# LEDclock_DCF77-RTC-BAT_2026-05-17.net
KiCad netlist of a schematic drawn in EasyEDA Pro
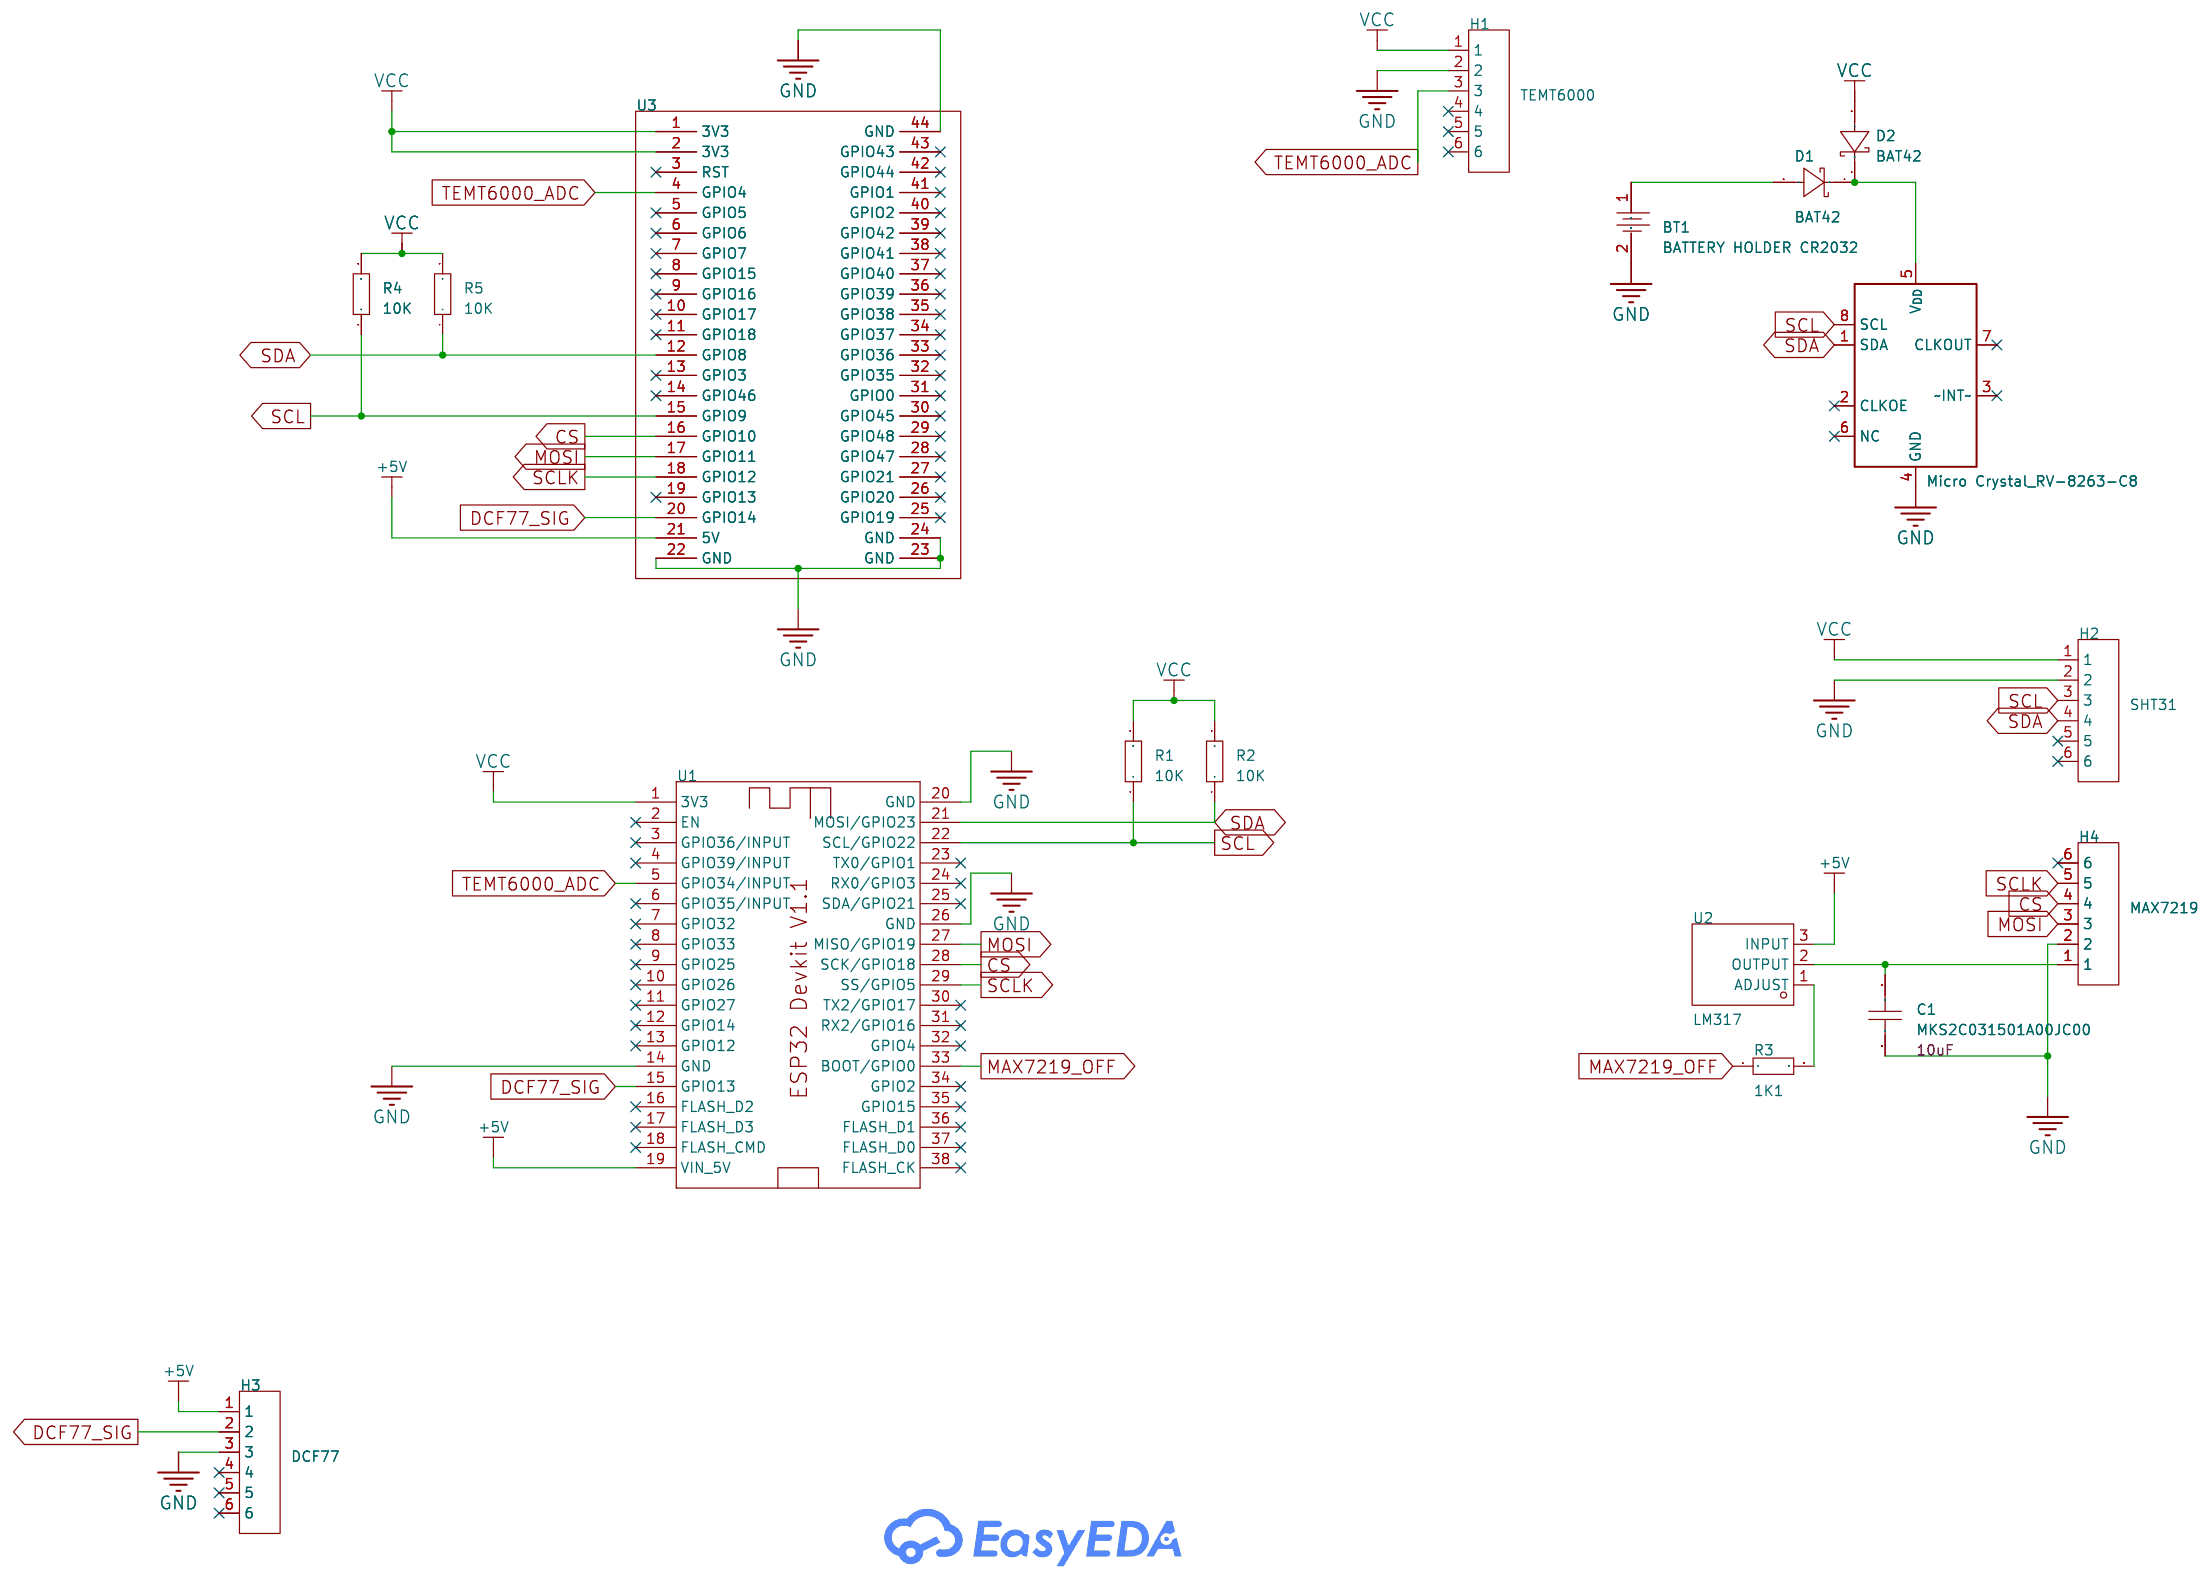
[diagram p0: schematic sheet]

(export (version "E")
  (design (tool "Eeschema 10.0.6"))
  (components
    (comp (ref "BT1")
      (value "BATTERY HOLDER CR2032")
      (footprint "easyedapro:BAT-TH_FBA25014-S02B2004K")
      (fields
        (field (name "Manufacturer Part") "FBA25014-S02B2004K")
        (field (name "Manufacturer") "TXGA(特思嘉)")
      )
      (libsource (lib "easyedapro") (part "FBA25014-S02B2004K"))
    )
    (comp (ref "C1")
      (value "MKS2C031501A00JC00")
      (footprint "easyedapro:CAP-TH_L7.2-W2.5-P5.00-D0.5-1")
      (fields (field (name "Manufacturer") "WIMA") (field (name "Capacitance") "10uF"))
      (libsource (lib "easyedapro") (part "MKS2C031501A00JC00"))
    )
    (comp (ref "D1")
      (value "BAT42")
      (footprint "easyedapro:DO-35_BD1.8-L4.1-P7.00-D0.5-RD")
      (fields (field (name "Manufacturer") "ST(意法半导体)"))
      (libsource (lib "easyedapro") (part "BAT42"))
    )
    (comp (ref "D2")
      (value "BAT42")
      (footprint "easyedapro:DO-35_BD1.8-L4.1-P7.00-D0.5-RD")
      (fields (field (name "Manufacturer") "ST(意法半导体)"))
      (libsource (lib "easyedapro") (part "BAT42"))
    )
    (comp (ref "H1")
      (value "TEMT6000")
      (footprint "easyedapro:CONN-TH_SSQ-106-03-G-S")
      (fields (field (name "Manufacturer") "SAMTEC"))
      (libsource (lib "easyedapro") (part "SSQ-106-03-G-S"))
    )
    (comp (ref "H2")
      (value "SHT31")
      (footprint "easyedapro:CONN-TH_SSQ-106-03-G-S")
      (fields (field (name "Manufacturer") "SAMTEC"))
      (libsource (lib "easyedapro") (part "SSQ-106-03-G-S"))
    )
    (comp (ref "H3")
      (value "DCF77")
      (footprint "easyedapro:CONN-TH_SSQ-106-03-G-S")
      (fields (field (name "Manufacturer") "SAMTEC"))
      (libsource (lib "easyedapro") (part "SSQ-106-03-G-S"))
    )
    (comp (ref "H4")
      (value "MAX7219")
      (footprint "easyedapro:CONN-TH_SSQ-106-03-G-S")
      (fields (field (name "Manufacturer") "SAMTEC"))
      (libsource (lib "easyedapro") (part "SSQ-106-03-G-S"))
    )
    (comp (ref "IC2")
      (value "RV-8263-C8")
      (footprint "easyedapro:Micro Crystal:RV-8263-C8")
      (libsource (lib "easyedapro") (part "Micro Crystal_RV-8263-C8"))
    )
    (comp (ref "R1") (value "10K") (footprint "easyedapro:R0603") (libsource (lib "easyedapro") (part "Res")))
    (comp (ref "R2") (value "10K") (footprint "easyedapro:R0603") (libsource (lib "easyedapro") (part "Res")))
    (comp (ref "R3") (value "1K1") (footprint "easyedapro:R0603") (libsource (lib "easyedapro") (part "Res")))
    (comp (ref "R4") (value "10K") (footprint "easyedapro:R0603") (libsource (lib "easyedapro") (part "Res")))
    (comp (ref "R5") (value "10K") (footprint "easyedapro:R0603") (libsource (lib "easyedapro") (part "Res")))
    (comp (ref "U1")
      (value "~")
      (footprint "easyedapro:ESP32-DEVKIT-V1.0-38PIN-PCB1.1")
      (libsource (lib "easyedapro") (part "ESP32-DEVKIT-V1.1"))
    )
    (comp (ref "U2")
      (value "LM317")
      (footprint "easyedapro:TO-220-3_L9.9-W4.5-P2.54-L-1")
      (fields (field (name "Manufacturer") "IDCHIP(英锐芯)"))
      (libsource (lib "easyedapro") (part "LM317_C7463411"))
    )
    (comp (ref "U3")
      (value "~")
      (footprint "easyedapro:ESP32-S3 ESP32-S3-DevKitC-1 N16R8")
      (libsource (lib "easyedapro") (part "ESP32-S3 ESP32-S3-DevKitC-1 N16R8"))
    )
  )
  (nets
    (net (code "1") (name "+5V") (class "Default")
      (node (ref "H3") (pin "1") (pinfunction "1_1") (pintype "unspecified"))
      (node (ref "U1") (pin "19") (pinfunction "VIN_5V_19") (pintype "bidirectional"))
      (node (ref "U2") (pin "3") (pinfunction "INPUT_3") (pintype "unspecified"))
      (node (ref "U3") (pin "21") (pinfunction "5V_21") (pintype "input"))
    )
    (net (code "2") (name "CS") (class "Default")
      (node (ref "H4") (pin "4") (pinfunction "4_4") (pintype "unspecified"))
      (node (ref "U1") (pin "28") (pinfunction "SCK/GPIO18_28") (pintype "bidirectional"))
      (node (ref "U3") (pin "16") (pinfunction "GPIO10_16") (pintype "input"))
    )
    (net (code "3") (name "DCF77_SIG") (class "Default")
      (node (ref "H3") (pin "2") (pinfunction "2_2") (pintype "unspecified"))
      (node (ref "U1") (pin "15") (pinfunction "GPIO13_15") (pintype "bidirectional"))
      (node (ref "U3") (pin "20") (pinfunction "GPIO14_20") (pintype "input"))
    )
    (net (code "4") (name "GND") (class "Default")
      (node (ref "BT1") (pin "2") (pinfunction "2_2") (pintype "input"))
      (node (ref "C1") (pin "1") (pinfunction "1_1") (pintype "unspecified"))
      (node (ref "H1") (pin "2") (pinfunction "2_2") (pintype "unspecified"))
      (node (ref "H2") (pin "2") (pinfunction "2_2") (pintype "unspecified"))
      (node (ref "H3") (pin "3") (pinfunction "3_3") (pintype "unspecified"))
      (node (ref "H4") (pin "2") (pinfunction "2_2") (pintype "unspecified"))
      (node (ref "IC2") (pin "4") (pinfunction "GND_4") (pintype "unspecified"))
      (node (ref "U1") (pin "14") (pinfunction "GND_14") (pintype "bidirectional"))
      (node (ref "U1") (pin "20") (pinfunction "GND_20") (pintype "bidirectional"))
      (node (ref "U1") (pin "26") (pinfunction "GND_26") (pintype "bidirectional"))
      (node (ref "U3") (pin "22") (pinfunction "GND_22") (pintype "input"))
      (node (ref "U3") (pin "23") (pinfunction "GND_23") (pintype "input"))
      (node (ref "U3") (pin "24") (pinfunction "GND_24") (pintype "input"))
      (node (ref "U3") (pin "44") (pinfunction "GND_44") (pintype "input"))
    )
    (net (code "5") (name "MAX7219_OFF") (class "Default")
      (node (ref "R3") (pin "1") (pinfunction "1_1") (pintype "input"))
      (node (ref "U1") (pin "33") (pinfunction "BOOT/GPIO0_33") (pintype "bidirectional"))
    )
    (net (code "6") (name "MOSI") (class "Default")
      (node (ref "H4") (pin "3") (pinfunction "3_3") (pintype "unspecified"))
      (node (ref "U1") (pin "27") (pinfunction "MISO/GPIO19_27") (pintype "bidirectional"))
      (node (ref "U3") (pin "17") (pinfunction "GPIO11_17") (pintype "input"))
    )
    (net (code "7") (name "Net-(D1-A)") (class "Default")
      (node (ref "BT1") (pin "1") (pinfunction "1_1") (pintype "input"))
      (node (ref "D1") (pin "2") (pinfunction "A_2") (pintype "unspecified"))
    )
    (net (code "8") (name "Net-(D1-K)") (class "Default")
      (node (ref "D1") (pin "1") (pinfunction "K_1") (pintype "unspecified"))
      (node (ref "D2") (pin "1") (pinfunction "K_1") (pintype "unspecified"))
      (node (ref "IC2") (pin "5") (pinfunction "V_{DD}_5") (pintype "unspecified"))
    )
    (net (code "9") (name "Net-(U2-ADJUST)") (class "Default")
      (node (ref "R3") (pin "2") (pinfunction "2_2") (pintype "input"))
      (node (ref "U2") (pin "1") (pinfunction "ADJUST_1") (pintype "unspecified"))
    )
    (net (code "10") (name "Net-(U2-OUTPUT)") (class "Default")
      (node (ref "C1") (pin "2") (pinfunction "2_2") (pintype "unspecified"))
      (node (ref "H4") (pin "1") (pinfunction "1_1") (pintype "unspecified"))
      (node (ref "U2") (pin "2") (pinfunction "OUTPUT_2") (pintype "unspecified"))
    )
    (net (code "11") (name "SCL") (class "Default")
      (node (ref "H2") (pin "3") (pinfunction "3_3") (pintype "unspecified"))
      (node (ref "IC2") (pin "8") (pinfunction "SCL_8") (pintype "input"))
      (node (ref "R1") (pin "1") (pinfunction "1_1") (pintype "input"))
      (node (ref "R4") (pin "1") (pinfunction "1_1") (pintype "input"))
      (node (ref "U1") (pin "22") (pinfunction "SCL/GPIO22_22") (pintype "bidirectional"))
      (node (ref "U3") (pin "15") (pinfunction "GPIO9_15") (pintype "input"))
    )
    (net (code "12") (name "SCLK") (class "Default")
      (node (ref "H4") (pin "5") (pinfunction "5_5") (pintype "unspecified"))
      (node (ref "U1") (pin "29") (pinfunction "SS/GPIO5_29") (pintype "bidirectional"))
      (node (ref "U3") (pin "18") (pinfunction "GPIO12_18") (pintype "input"))
    )
    (net (code "13") (name "SDA") (class "Default")
      (node (ref "H2") (pin "4") (pinfunction "4_4") (pintype "unspecified"))
      (node (ref "IC2") (pin "1") (pinfunction "SDA_1") (pintype "bidirectional"))
      (node (ref "R2") (pin "1") (pinfunction "1_1") (pintype "input"))
      (node (ref "R5") (pin "1") (pinfunction "1_1") (pintype "input"))
      (node (ref "U1") (pin "21") (pinfunction "MOSI/GPIO23_21") (pintype "bidirectional"))
      (node (ref "U3") (pin "12") (pinfunction "GPIO8_12") (pintype "input"))
    )
    (net (code "14") (name "TEMT6000_ADC") (class "Default")
      (node (ref "H1") (pin "3") (pinfunction "3_3") (pintype "unspecified"))
      (node (ref "U1") (pin "5") (pinfunction "GPIO34/INPUT_5") (pintype "bidirectional"))
      (node (ref "U3") (pin "4") (pinfunction "GPIO4_4") (pintype "input"))
    )
    (net (code "15") (name "VCC") (class "Default")
      (node (ref "D2") (pin "2") (pinfunction "A_2") (pintype "unspecified"))
      (node (ref "H1") (pin "1") (pinfunction "1_1") (pintype "unspecified"))
      (node (ref "H2") (pin "1") (pinfunction "1_1") (pintype "unspecified"))
      (node (ref "R1") (pin "2") (pinfunction "2_2") (pintype "input"))
      (node (ref "R2") (pin "2") (pinfunction "2_2") (pintype "input"))
      (node (ref "R4") (pin "2") (pinfunction "2_2") (pintype "input"))
      (node (ref "R5") (pin "2") (pinfunction "2_2") (pintype "input"))
      (node (ref "U1") (pin "1") (pinfunction "3V3_1") (pintype "bidirectional"))
      (node (ref "U3") (pin "1") (pinfunction "3V3_1") (pintype "input"))
      (node (ref "U3") (pin "2") (pinfunction "3V3_2") (pintype "input"))
    )
    (net (code "16") (name "unconnected-(H1-Pad4)") (class "Default")
      (node (ref "H1") (pin "4") (pinfunction "4_4") (pintype "unspecified+no_connect"))
    )
    (net (code "17") (name "unconnected-(H1-Pad5)") (class "Default")
      (node (ref "H1") (pin "5") (pinfunction "5_5") (pintype "unspecified+no_connect"))
    )
    (net (code "18") (name "unconnected-(H1-Pad6)") (class "Default")
      (node (ref "H1") (pin "6") (pinfunction "6_6") (pintype "unspecified+no_connect"))
    )
    (net (code "19") (name "unconnected-(H2-Pad5)") (class "Default")
      (node (ref "H2") (pin "5") (pinfunction "5_5") (pintype "unspecified+no_connect"))
    )
    (net (code "20") (name "unconnected-(H2-Pad6)") (class "Default")
      (node (ref "H2") (pin "6") (pinfunction "6_6") (pintype "unspecified+no_connect"))
    )
    (net (code "21") (name "unconnected-(H3-Pad4)") (class "Default")
      (node (ref "H3") (pin "4") (pinfunction "4_4") (pintype "unspecified+no_connect"))
    )
    (net (code "22") (name "unconnected-(H3-Pad5)") (class "Default")
      (node (ref "H3") (pin "5") (pinfunction "5_5") (pintype "unspecified+no_connect"))
    )
    (net (code "23") (name "unconnected-(H3-Pad6)") (class "Default")
      (node (ref "H3") (pin "6") (pinfunction "6_6") (pintype "unspecified+no_connect"))
    )
    (net (code "24") (name "unconnected-(H4-Pad6)") (class "Default")
      (node (ref "H4") (pin "6") (pinfunction "6_6") (pintype "unspecified+no_connect"))
    )
    (net (code "25") (name "unconnected-(IC2-CLKOE-Pad2)") (class "Default")
      (node (ref "IC2") (pin "2") (pinfunction "CLKOE_2") (pintype "input+no_connect"))
    )
    (net (code "26") (name "unconnected-(IC2-CLKOUT-Pad7)") (class "Default")
      (node (ref "IC2") (pin "7") (pinfunction "CLKOUT_7") (pintype "output+no_connect"))
    )
    (net (code "27") (name "unconnected-(IC2-NC-Pad6)") (class "Default")
      (node (ref "IC2") (pin "6") (pinfunction "NC_6") (pintype "unspecified+no_connect"))
    )
    (net (code "28") (name "unconnected-(IC2-~INT~-Pad3)") (class "Default")
      (node (ref "IC2") (pin "3") (pinfunction "~INT~_3") (pintype "output+no_connect"))
    )
    (net (code "29") (name "unconnected-(U1-EN-Pad2)") (class "Default")
      (node (ref "U1") (pin "2") (pinfunction "EN_2") (pintype "bidirectional+no_connect"))
    )
    (net (code "30") (name "unconnected-(U1-FLASH_CK-Pad38)") (class "Default")
      (node (ref "U1") (pin "38") (pinfunction "FLASH_CK_38") (pintype "bidirectional+no_connect"))
    )
    (net (code "31") (name "unconnected-(U1-FLASH_CMD-Pad18)") (class "Default")
      (node (ref "U1") (pin "18") (pinfunction "FLASH_CMD_18") (pintype "bidirectional+no_connect"))
    )
    (net (code "32") (name "unconnected-(U1-FLASH_D0-Pad37)") (class "Default")
      (node (ref "U1") (pin "37") (pinfunction "FLASH_D0_37") (pintype "bidirectional+no_connect"))
    )
    (net (code "33") (name "unconnected-(U1-FLASH_D1-Pad36)") (class "Default")
      (node (ref "U1") (pin "36") (pinfunction "FLASH_D1_36") (pintype "bidirectional+no_connect"))
    )
    (net (code "34") (name "unconnected-(U1-FLASH_D2-Pad16)") (class "Default")
      (node (ref "U1") (pin "16") (pinfunction "FLASH_D2_16") (pintype "bidirectional+no_connect"))
    )
    (net (code "35") (name "unconnected-(U1-FLASH_D3-Pad17)") (class "Default")
      (node (ref "U1") (pin "17") (pinfunction "FLASH_D3_17") (pintype "bidirectional+no_connect"))
    )
    (net (code "36") (name "unconnected-(U1-GPIO2-Pad34)") (class "Default")
      (node (ref "U1") (pin "34") (pinfunction "GPIO2_34") (pintype "bidirectional+no_connect"))
    )
    (net (code "37") (name "unconnected-(U1-GPIO4-Pad32)") (class "Default")
      (node (ref "U1") (pin "32") (pinfunction "GPIO4_32") (pintype "bidirectional+no_connect"))
    )
    (net (code "38") (name "unconnected-(U1-GPIO12-Pad13)") (class "Default")
      (node (ref "U1") (pin "13") (pinfunction "GPIO12_13") (pintype "bidirectional+no_connect"))
    )
    (net (code "39") (name "unconnected-(U1-GPIO14-Pad12)") (class "Default")
      (node (ref "U1") (pin "12") (pinfunction "GPIO14_12") (pintype "bidirectional+no_connect"))
    )
    (net (code "40") (name "unconnected-(U1-GPIO15-Pad35)") (class "Default")
      (node (ref "U1") (pin "35") (pinfunction "GPIO15_35") (pintype "bidirectional+no_connect"))
    )
    (net (code "41") (name "unconnected-(U1-GPIO25-Pad9)") (class "Default")
      (node (ref "U1") (pin "9") (pinfunction "GPIO25_9") (pintype "bidirectional+no_connect"))
    )
    (net (code "42") (name "unconnected-(U1-GPIO26-Pad10)") (class "Default")
      (node (ref "U1") (pin "10") (pinfunction "GPIO26_10") (pintype "bidirectional+no_connect"))
    )
    (net (code "43") (name "unconnected-(U1-GPIO27-Pad11)") (class "Default")
      (node (ref "U1") (pin "11") (pinfunction "GPIO27_11") (pintype "bidirectional+no_connect"))
    )
    (net (code "44") (name "unconnected-(U1-GPIO32-Pad7)") (class "Default")
      (node (ref "U1") (pin "7") (pinfunction "GPIO32_7") (pintype "bidirectional+no_connect"))
    )
    (net (code "45") (name "unconnected-(U1-GPIO33-Pad8)") (class "Default")
      (node (ref "U1") (pin "8") (pinfunction "GPIO33_8") (pintype "bidirectional+no_connect"))
    )
    (net (code "46") (name "unconnected-(U1-GPIO35{slash}INPUT-Pad6)") (class "Default")
      (node (ref "U1") (pin "6") (pinfunction "GPIO35/INPUT_6") (pintype "bidirectional+no_connect"))
    )
    (net (code "47") (name "unconnected-(U1-GPIO36{slash}INPUT-Pad3)") (class "Default")
      (node (ref "U1") (pin "3") (pinfunction "GPIO36/INPUT_3") (pintype "bidirectional+no_connect"))
    )
    (net (code "48") (name "unconnected-(U1-GPIO39{slash}INPUT-Pad4)") (class "Default")
      (node (ref "U1") (pin "4") (pinfunction "GPIO39/INPUT_4") (pintype "bidirectional+no_connect"))
    )
    (net (code "49") (name "unconnected-(U1-RX0{slash}GPIO3-Pad24)") (class "Default")
      (node (ref "U1") (pin "24") (pinfunction "RX0/GPIO3_24") (pintype "bidirectional+no_connect"))
    )
    (net (code "50") (name "unconnected-(U1-RX2{slash}GPIO16-Pad31)") (class "Default")
      (node (ref "U1") (pin "31") (pinfunction "RX2/GPIO16_31") (pintype "bidirectional+no_connect"))
    )
    (net (code "51") (name "unconnected-(U1-SDA{slash}GPIO21-Pad25)") (class "Default")
      (node (ref "U1") (pin "25") (pinfunction "SDA/GPIO21_25") (pintype "bidirectional+no_connect"))
    )
    (net (code "52") (name "unconnected-(U1-TX0{slash}GPIO1-Pad23)") (class "Default")
      (node (ref "U1") (pin "23") (pinfunction "TX0/GPIO1_23") (pintype "bidirectional+no_connect"))
    )
    (net (code "53") (name "unconnected-(U1-TX2{slash}GPIO17-Pad30)") (class "Default")
      (node (ref "U1") (pin "30") (pinfunction "TX2/GPIO17_30") (pintype "bidirectional+no_connect"))
    )
    (net (code "54") (name "unconnected-(U3-GPIO0-Pad31)") (class "Default")
      (node (ref "U3") (pin "31") (pinfunction "GPIO0_31") (pintype "input+no_connect"))
    )
    (net (code "55") (name "unconnected-(U3-GPIO1-Pad41)") (class "Default")
      (node (ref "U3") (pin "41") (pinfunction "GPIO1_41") (pintype "input+no_connect"))
    )
    (net (code "56") (name "unconnected-(U3-GPIO2-Pad40)") (class "Default")
      (node (ref "U3") (pin "40") (pinfunction "GPIO2_40") (pintype "input+no_connect"))
    )
    (net (code "57") (name "unconnected-(U3-GPIO3-Pad13)") (class "Default")
      (node (ref "U3") (pin "13") (pinfunction "GPIO3_13") (pintype "input+no_connect"))
    )
    (net (code "58") (name "unconnected-(U3-GPIO5-Pad5)") (class "Default")
      (node (ref "U3") (pin "5") (pinfunction "GPIO5_5") (pintype "input+no_connect"))
    )
    (net (code "59") (name "unconnected-(U3-GPIO6-Pad6)") (class "Default")
      (node (ref "U3") (pin "6") (pinfunction "GPIO6_6") (pintype "input+no_connect"))
    )
    (net (code "60") (name "unconnected-(U3-GPIO7-Pad7)") (class "Default")
      (node (ref "U3") (pin "7") (pinfunction "GPIO7_7") (pintype "input+no_connect"))
    )
    (net (code "61") (name "unconnected-(U3-GPIO13-Pad19)") (class "Default")
      (node (ref "U3") (pin "19") (pinfunction "GPIO13_19") (pintype "input+no_connect"))
    )
    (net (code "62") (name "unconnected-(U3-GPIO15-Pad8)") (class "Default")
      (node (ref "U3") (pin "8") (pinfunction "GPIO15_8") (pintype "input+no_connect"))
    )
    (net (code "63") (name "unconnected-(U3-GPIO16-Pad9)") (class "Default")
      (node (ref "U3") (pin "9") (pinfunction "GPIO16_9") (pintype "input+no_connect"))
    )
    (net (code "64") (name "unconnected-(U3-GPIO17-Pad10)") (class "Default")
      (node (ref "U3") (pin "10") (pinfunction "GPIO17_10") (pintype "input+no_connect"))
    )
    (net (code "65") (name "unconnected-(U3-GPIO18-Pad11)") (class "Default")
      (node (ref "U3") (pin "11") (pinfunction "GPIO18_11") (pintype "input+no_connect"))
    )
    (net (code "66") (name "unconnected-(U3-GPIO19-Pad25)") (class "Default")
      (node (ref "U3") (pin "25") (pinfunction "GPIO19_25") (pintype "input+no_connect"))
    )
    (net (code "67") (name "unconnected-(U3-GPIO20-Pad26)") (class "Default")
      (node (ref "U3") (pin "26") (pinfunction "GPIO20_26") (pintype "input+no_connect"))
    )
    (net (code "68") (name "unconnected-(U3-GPIO21-Pad27)") (class "Default")
      (node (ref "U3") (pin "27") (pinfunction "GPIO21_27") (pintype "input+no_connect"))
    )
    (net (code "69") (name "unconnected-(U3-GPIO35-Pad32)") (class "Default")
      (node (ref "U3") (pin "32") (pinfunction "GPIO35_32") (pintype "input+no_connect"))
    )
    (net (code "70") (name "unconnected-(U3-GPIO36-Pad33)") (class "Default")
      (node (ref "U3") (pin "33") (pinfunction "GPIO36_33") (pintype "input+no_connect"))
    )
    (net (code "71") (name "unconnected-(U3-GPIO37-Pad34)") (class "Default")
      (node (ref "U3") (pin "34") (pinfunction "GPIO37_34") (pintype "input+no_connect"))
    )
    (net (code "72") (name "unconnected-(U3-GPIO38-Pad35)") (class "Default")
      (node (ref "U3") (pin "35") (pinfunction "GPIO38_35") (pintype "input+no_connect"))
    )
    (net (code "73") (name "unconnected-(U3-GPIO39-Pad36)") (class "Default")
      (node (ref "U3") (pin "36") (pinfunction "GPIO39_36") (pintype "input+no_connect"))
    )
    (net (code "74") (name "unconnected-(U3-GPIO40-Pad37)") (class "Default")
      (node (ref "U3") (pin "37") (pinfunction "GPIO40_37") (pintype "input+no_connect"))
    )
    (net (code "75") (name "unconnected-(U3-GPIO41-Pad38)") (class "Default")
      (node (ref "U3") (pin "38") (pinfunction "GPIO41_38") (pintype "input+no_connect"))
    )
    (net (code "76") (name "unconnected-(U3-GPIO42-Pad39)") (class "Default")
      (node (ref "U3") (pin "39") (pinfunction "GPIO42_39") (pintype "input+no_connect"))
    )
    (net (code "77") (name "unconnected-(U3-GPIO43-Pad43)") (class "Default")
      (node (ref "U3") (pin "43") (pinfunction "GPIO43_43") (pintype "input+no_connect"))
    )
    (net (code "78") (name "unconnected-(U3-GPIO44-Pad42)") (class "Default")
      (node (ref "U3") (pin "42") (pinfunction "GPIO44_42") (pintype "input+no_connect"))
    )
    (net (code "79") (name "unconnected-(U3-GPIO45-Pad30)") (class "Default")
      (node (ref "U3") (pin "30") (pinfunction "GPIO45_30") (pintype "input+no_connect"))
    )
    (net (code "80") (name "unconnected-(U3-GPIO46-Pad14)") (class "Default")
      (node (ref "U3") (pin "14") (pinfunction "GPIO46_14") (pintype "input+no_connect"))
    )
    (net (code "81") (name "unconnected-(U3-GPIO47-Pad28)") (class "Default")
      (node (ref "U3") (pin "28") (pinfunction "GPIO47_28") (pintype "input+no_connect"))
    )
    (net (code "82") (name "unconnected-(U3-GPIO48-Pad29)") (class "Default")
      (node (ref "U3") (pin "29") (pinfunction "GPIO48_29") (pintype "input+no_connect"))
    )
    (net (code "83") (name "unconnected-(U3-RST-Pad3)") (class "Default")
      (node (ref "U3") (pin "3") (pinfunction "RST_3") (pintype "input+no_connect"))
    )
  )
)
